# public_ASADASIoTV1.net
KiCad netlist of a schematic drawn in EAGLE
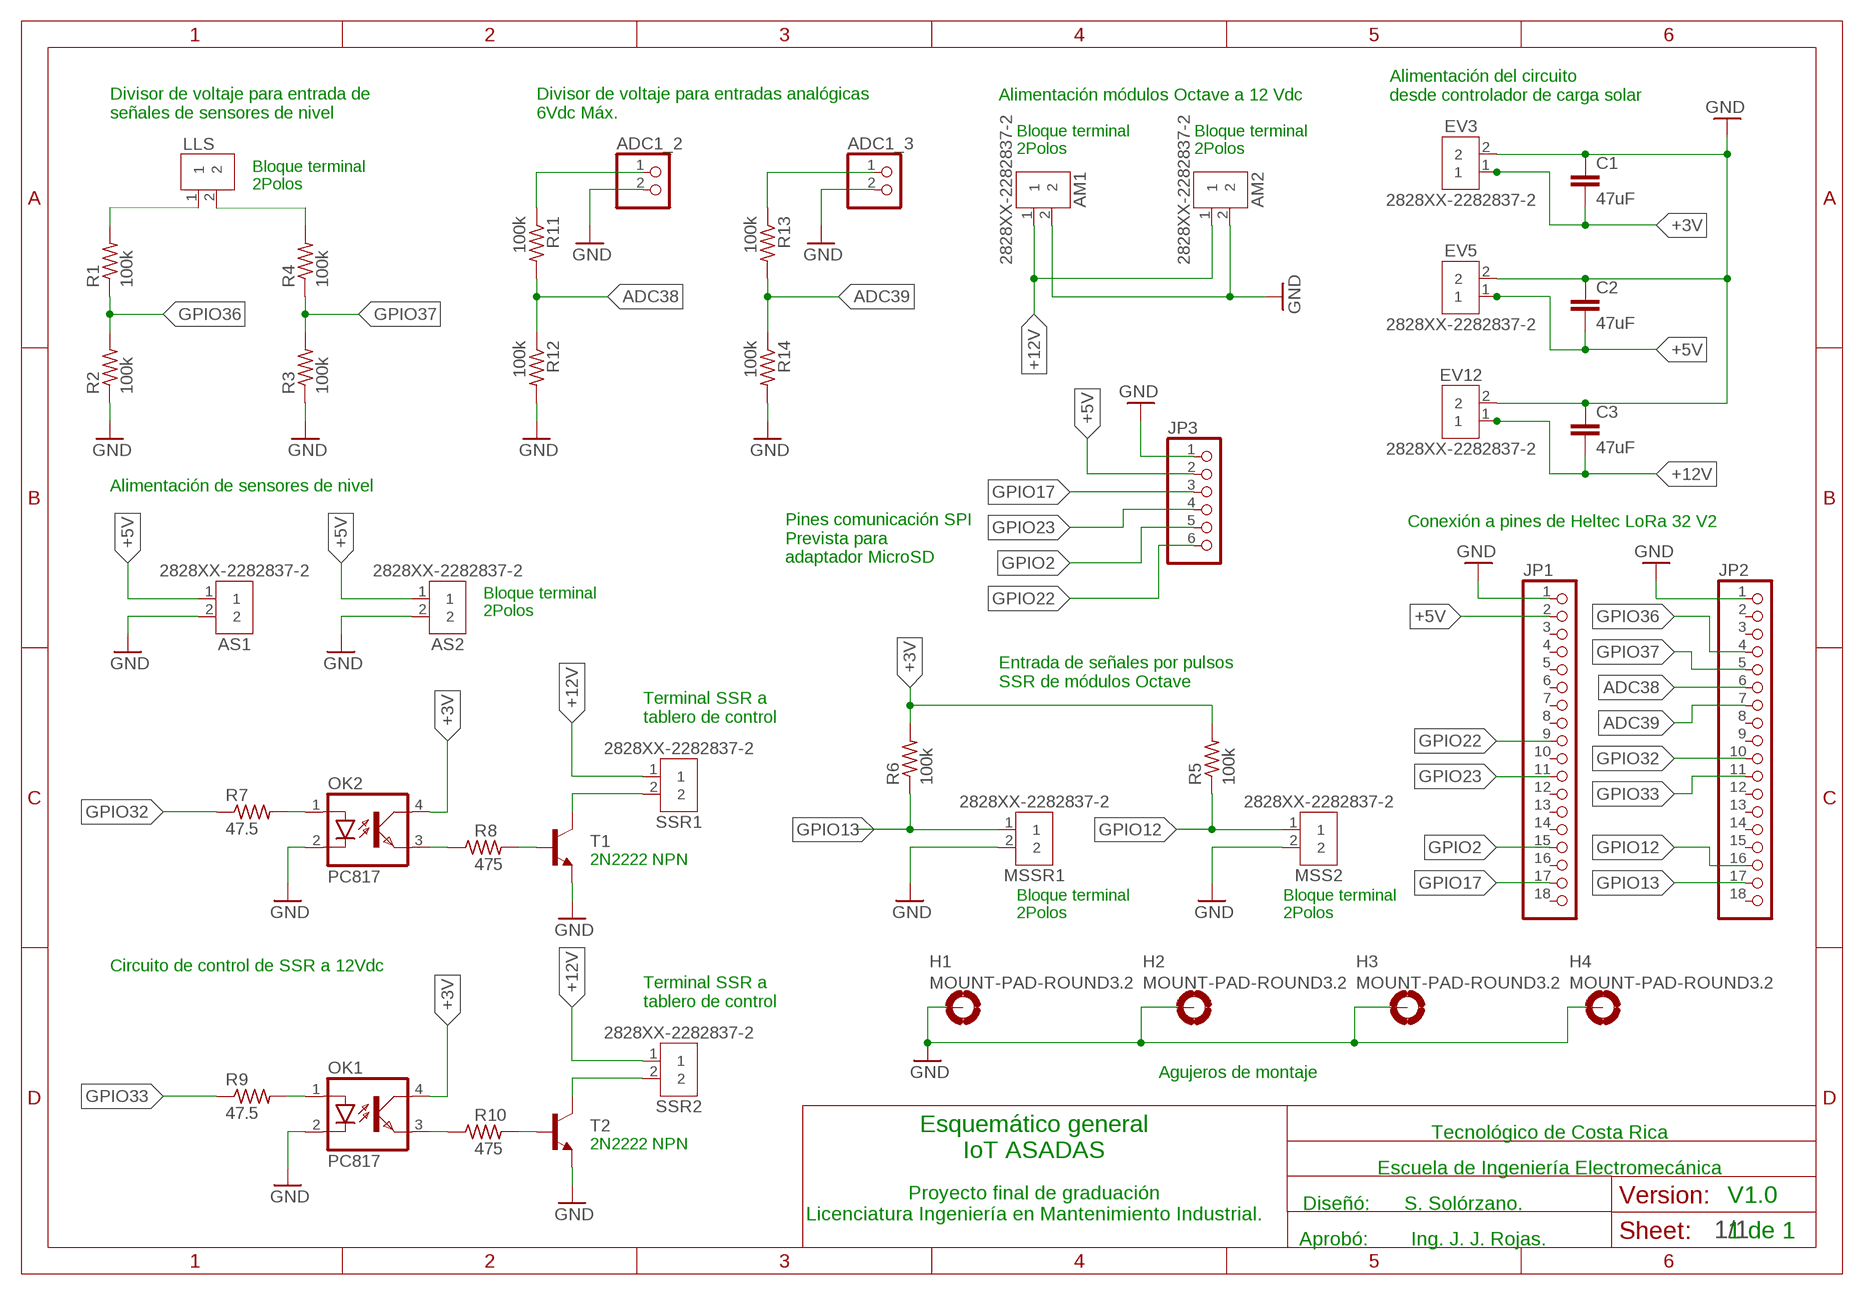
[diagram p0: schematic, sheet 1]

(export (version "E")
  (design (tool "Eeschema 10.0.6"))
  (components
    (comp (ref "ADC1_2")
      (value "PINHD-1X2")
      (footprint "eagle-import:1X02")
      (libsource (lib "eagle-import") (part "PINHD-1X2"))
    )
    (comp (ref "ADC1_3")
      (value "PINHD-1X2")
      (footprint "eagle-import:1X02")
      (libsource (lib "eagle-import") (part "PINHD-1X2"))
    )
    (comp (ref "AM1")
      (value "2828XX-2282837-2")
      (footprint "eagle-import:TERMBLK_508-2N")
      (fields (field (name "MANUFACTURER") "TE Connectivity") (field (name "MPN") "282837-2"))
      (libsource (lib "eagle-import") (part "2828XX-2282837-2"))
    )
    (comp (ref "AM2")
      (value "2828XX-2282837-2")
      (footprint "eagle-import:TERMBLK_508-2N")
      (fields (field (name "MANUFACTURER") "TE Connectivity") (field (name "MPN") "282837-2"))
      (libsource (lib "eagle-import") (part "2828XX-2282837-2"))
    )
    (comp (ref "AS1")
      (value "2828XX-2282837-2")
      (footprint "eagle-import:TERMBLK_508-2N")
      (fields (field (name "MANUFACTURER") "TE Connectivity") (field (name "MPN") "282837-2"))
      (libsource (lib "eagle-import") (part "2828XX-2282837-2"))
    )
    (comp (ref "AS2")
      (value "2828XX-2282837-2")
      (footprint "eagle-import:TERMBLK_508-2N")
      (fields (field (name "MANUFACTURER") "TE Connectivity") (field (name "MPN") "282837-2"))
      (libsource (lib "eagle-import") (part "2828XX-2282837-2"))
    )
    (comp (ref "C1")
      (value "47uF")
      (footprint "eagle-import:C2.5-5")
      (libsource (lib "eagle-import") (part "C2.5/5"))
    )
    (comp (ref "C2")
      (value "47uF")
      (footprint "eagle-import:C2.5-5")
      (libsource (lib "eagle-import") (part "C2.5/5"))
    )
    (comp (ref "C3")
      (value "47uF")
      (footprint "eagle-import:C2.5-5")
      (libsource (lib "eagle-import") (part "C2.5/5"))
    )
    (comp (ref "EV3")
      (value "2828XX-2282837-2")
      (footprint "eagle-import:TERMBLK_508-2N")
      (fields (field (name "MANUFACTURER") "TE Connectivity") (field (name "MPN") "282837-2"))
      (libsource (lib "eagle-import") (part "2828XX-2282837-2"))
    )
    (comp (ref "EV5")
      (value "2828XX-2282837-2")
      (footprint "eagle-import:TERMBLK_508-2N")
      (fields (field (name "MANUFACTURER") "TE Connectivity") (field (name "MPN") "282837-2"))
      (libsource (lib "eagle-import") (part "2828XX-2282837-2"))
    )
    (comp (ref "EV12")
      (value "2828XX-2282837-2")
      (footprint "eagle-import:TERMBLK_508-2N")
      (fields (field (name "MANUFACTURER") "TE Connectivity") (field (name "MPN") "282837-2"))
      (libsource (lib "eagle-import") (part "2828XX-2282837-2"))
    )
    (comp (ref "H1")
      (value "MOUNT-PAD-ROUND3.2")
      (footprint "eagle-import:3,2-PAD")
      (libsource (lib "eagle-import") (part "MOUNT-PAD-ROUND3.2"))
    )
    (comp (ref "H2")
      (value "MOUNT-PAD-ROUND3.2")
      (footprint "eagle-import:3,2-PAD")
      (libsource (lib "eagle-import") (part "MOUNT-PAD-ROUND3.2"))
    )
    (comp (ref "H3")
      (value "MOUNT-PAD-ROUND3.2")
      (footprint "eagle-import:3,2-PAD")
      (libsource (lib "eagle-import") (part "MOUNT-PAD-ROUND3.2"))
    )
    (comp (ref "H4")
      (value "MOUNT-PAD-ROUND3.2")
      (footprint "eagle-import:3,2-PAD")
      (libsource (lib "eagle-import") (part "MOUNT-PAD-ROUND3.2"))
    )
    (comp (ref "JP1")
      (value "PINHD-1X18")
      (footprint "eagle-import:1X18")
      (libsource (lib "eagle-import") (part "PINHD-1X18"))
    )
    (comp (ref "JP2")
      (value "PINHD-1X18")
      (footprint "eagle-import:1X18")
      (libsource (lib "eagle-import") (part "PINHD-1X18"))
    )
    (comp (ref "JP3")
      (value "PINHD-1X6")
      (footprint "eagle-import:1X06")
      (libsource (lib "eagle-import") (part "PINHD-1X6"))
    )
    (comp (ref "LLS")
      (value "2828XX-2282837-2")
      (footprint "eagle-import:TERMBLK_508-2N")
      (fields (field (name "MANUFACTURER") "TE Connectivity") (field (name "MPN") "282837-2"))
      (libsource (lib "eagle-import") (part "2828XX-2282837-2"))
    )
    (comp (ref "MSS2")
      (value "2828XX-2282837-2")
      (footprint "eagle-import:TERMBLK_508-2N")
      (fields (field (name "MANUFACTURER") "TE Connectivity") (field (name "MPN") "282837-2"))
      (libsource (lib "eagle-import") (part "2828XX-2282837-2"))
    )
    (comp (ref "MSSR1")
      (value "2828XX-2282837-2")
      (footprint "eagle-import:TERMBLK_508-2N")
      (fields (field (name "MANUFACTURER") "TE Connectivity") (field (name "MPN") "282837-2"))
      (libsource (lib "eagle-import") (part "2828XX-2282837-2"))
    )
    (comp (ref "OK1")
      (value "PC817")
      (footprint "eagle-import:DIL04")
      (fields (field (name "MPN") "PC817X4J000F"))
      (libsource (lib "eagle-import") (part "PC817"))
    )
    (comp (ref "OK2")
      (value "PC817")
      (footprint "eagle-import:DIL04")
      (fields (field (name "MPN") "PC817X4J000F"))
      (libsource (lib "eagle-import") (part "PC817"))
    )
    (comp (ref "R1")
      (value "100k")
      (footprint "eagle-import:R0805")
      (libsource (lib "eagle-import") (part "R-US_R0805"))
    )
    (comp (ref "R2")
      (value "100k")
      (footprint "eagle-import:R0805")
      (libsource (lib "eagle-import") (part "R-US_R0805"))
    )
    (comp (ref "R3")
      (value "100k")
      (footprint "eagle-import:R0805")
      (libsource (lib "eagle-import") (part "R-US_R0805"))
    )
    (comp (ref "R4")
      (value "100k")
      (footprint "eagle-import:R0805")
      (libsource (lib "eagle-import") (part "R-US_R0805"))
    )
    (comp (ref "R5")
      (value "100k")
      (footprint "eagle-import:R0805")
      (libsource (lib "eagle-import") (part "R-US_R0805"))
    )
    (comp (ref "R6")
      (value "100k")
      (footprint "eagle-import:R0805")
      (libsource (lib "eagle-import") (part "R-US_R0805"))
    )
    (comp (ref "R7")
      (value "47.5")
      (footprint "eagle-import:R0805")
      (libsource (lib "eagle-import") (part "R-US_R0805"))
    )
    (comp (ref "R8")
      (value "475")
      (footprint "eagle-import:R0805")
      (libsource (lib "eagle-import") (part "R-US_R0805"))
    )
    (comp (ref "R9")
      (value "47.5")
      (footprint "eagle-import:R0805")
      (libsource (lib "eagle-import") (part "R-US_R0805"))
    )
    (comp (ref "R10")
      (value "475")
      (footprint "eagle-import:R0805")
      (libsource (lib "eagle-import") (part "R-US_R0805"))
    )
    (comp (ref "R11")
      (value "100k")
      (footprint "eagle-import:R0805")
      (libsource (lib "eagle-import") (part "R-US_R0805"))
    )
    (comp (ref "R12")
      (value "100k")
      (footprint "eagle-import:R0805")
      (libsource (lib "eagle-import") (part "R-US_R0805"))
    )
    (comp (ref "R13")
      (value "100k")
      (footprint "eagle-import:R0805")
      (libsource (lib "eagle-import") (part "R-US_R0805"))
    )
    (comp (ref "R14")
      (value "100k")
      (footprint "eagle-import:R0805")
      (libsource (lib "eagle-import") (part "R-US_R0805"))
    )
    (comp (ref "SSR1")
      (value "2828XX-2282837-2")
      (footprint "eagle-import:TERMBLK_508-2N")
      (fields (field (name "MANUFACTURER") "TE Connectivity") (field (name "MPN") "282837-2"))
      (libsource (lib "eagle-import") (part "2828XX-2282837-2"))
    )
    (comp (ref "SSR2")
      (value "2828XX-2282837-2")
      (footprint "eagle-import:TERMBLK_508-2N")
      (fields (field (name "MANUFACTURER") "TE Connectivity") (field (name "MPN") "282837-2"))
      (libsource (lib "eagle-import") (part "2828XX-2282837-2"))
    )
    (comp (ref "T1")
      (value "2N3904")
      (footprint "eagle-import:TO92")
      (libsource (lib "eagle-import") (part "2N3904"))
    )
    (comp (ref "T2")
      (value "2N3904")
      (footprint "eagle-import:TO92")
      (libsource (lib "eagle-import") (part "2N3904"))
    )
  )
  (nets
    (net (code "1") (name "+3V") (class "Default")
      (node (ref "C1") (pin "2") (pinfunction "2_2") (pintype "passive"))
      (node (ref "EV3") (pin "1") (pinfunction "1_1") (pintype "bidirectional"))
      (node (ref "OK1") (pin "4") (pinfunction "COL_4") (pintype "passive"))
      (node (ref "OK2") (pin "4") (pinfunction "COL_4") (pintype "passive"))
      (node (ref "R5") (pin "2") (pinfunction "2_2") (pintype "passive"))
      (node (ref "R6") (pin "2") (pinfunction "2_2") (pintype "passive"))
    )
    (net (code "2") (name "+5V") (class "Default")
      (node (ref "AS1") (pin "1") (pinfunction "1_1") (pintype "bidirectional"))
      (node (ref "AS2") (pin "1") (pinfunction "1_1") (pintype "bidirectional"))
      (node (ref "C2") (pin "2") (pinfunction "2_2") (pintype "passive"))
      (node (ref "EV5") (pin "1") (pinfunction "1_1") (pintype "bidirectional"))
      (node (ref "JP1") (pin "2") (pinfunction "2_2") (pintype "passive"))
      (node (ref "JP3") (pin "2") (pinfunction "2_2") (pintype "passive"))
    )
    (net (code "3") (name "+12V") (class "Default")
      (node (ref "AM1") (pin "1") (pinfunction "1_1") (pintype "bidirectional"))
      (node (ref "AM2") (pin "1") (pinfunction "1_1") (pintype "bidirectional"))
      (node (ref "C3") (pin "2") (pinfunction "2_2") (pintype "passive"))
      (node (ref "EV12") (pin "1") (pinfunction "1_1") (pintype "bidirectional"))
      (node (ref "SSR1") (pin "1") (pinfunction "1_1") (pintype "bidirectional"))
      (node (ref "SSR2") (pin "1") (pinfunction "1_1") (pintype "bidirectional"))
    )
    (net (code "4") (name "ADC38") (class "Default")
      (node (ref "JP2") (pin "6") (pinfunction "6_6") (pintype "passive"))
      (node (ref "R11") (pin "2") (pinfunction "2_2") (pintype "passive"))
      (node (ref "R12") (pin "1") (pinfunction "1_1") (pintype "passive"))
    )
    (net (code "5") (name "ADC39") (class "Default")
      (node (ref "JP2") (pin "7") (pinfunction "7_7") (pintype "passive"))
      (node (ref "R13") (pin "2") (pinfunction "2_2") (pintype "passive"))
      (node (ref "R14") (pin "1") (pinfunction "1_1") (pintype "passive"))
    )
    (net (code "6") (name "GND") (class "Default")
      (node (ref "ADC1_2") (pin "2") (pinfunction "2_2") (pintype "passive"))
      (node (ref "ADC1_3") (pin "2") (pinfunction "2_2") (pintype "passive"))
      (node (ref "AM1") (pin "2") (pinfunction "2_2") (pintype "bidirectional"))
      (node (ref "AM2") (pin "2") (pinfunction "2_2") (pintype "bidirectional"))
      (node (ref "AS1") (pin "2") (pinfunction "2_2") (pintype "bidirectional"))
      (node (ref "AS2") (pin "2") (pinfunction "2_2") (pintype "bidirectional"))
      (node (ref "C1") (pin "1") (pinfunction "1_1") (pintype "passive"))
      (node (ref "C2") (pin "1") (pinfunction "1_1") (pintype "passive"))
      (node (ref "C3") (pin "1") (pinfunction "1_1") (pintype "passive"))
      (node (ref "EV12") (pin "2") (pinfunction "2_2") (pintype "bidirectional"))
      (node (ref "EV3") (pin "2") (pinfunction "2_2") (pintype "bidirectional"))
      (node (ref "EV5") (pin "2") (pinfunction "2_2") (pintype "bidirectional"))
      (node (ref "H1") (pin "B3,2") (pinfunction "MOUNT_B3,2") (pintype "passive"))
      (node (ref "H2") (pin "B3,2") (pinfunction "MOUNT_B3,2") (pintype "passive"))
      (node (ref "H3") (pin "B3,2") (pinfunction "MOUNT_B3,2") (pintype "passive"))
      (node (ref "H4") (pin "B3,2") (pinfunction "MOUNT_B3,2") (pintype "passive"))
      (node (ref "JP1") (pin "1") (pinfunction "1_1") (pintype "passive"))
      (node (ref "JP2") (pin "1") (pinfunction "1_1") (pintype "passive"))
      (node (ref "JP3") (pin "1") (pinfunction "1_1") (pintype "passive"))
      (node (ref "MSS2") (pin "2") (pinfunction "2_2") (pintype "bidirectional"))
      (node (ref "MSSR1") (pin "2") (pinfunction "2_2") (pintype "bidirectional"))
      (node (ref "OK1") (pin "2") (pinfunction "C_2") (pintype "passive"))
      (node (ref "OK2") (pin "2") (pinfunction "C_2") (pintype "passive"))
      (node (ref "R12") (pin "2") (pinfunction "2_2") (pintype "passive"))
      (node (ref "R14") (pin "2") (pinfunction "2_2") (pintype "passive"))
      (node (ref "R2") (pin "1") (pinfunction "1_1") (pintype "passive"))
      (node (ref "R3") (pin "1") (pinfunction "1_1") (pintype "passive"))
      (node (ref "T1") (pin "3") (pinfunction "E_3") (pintype "passive"))
      (node (ref "T2") (pin "3") (pinfunction "E_3") (pintype "passive"))
    )
    (net (code "7") (name "GPIO2") (class "Default")
      (node (ref "JP1") (pin "15") (pinfunction "15_15") (pintype "passive"))
      (node (ref "JP3") (pin "5") (pinfunction "5_5") (pintype "passive"))
    )
    (net (code "8") (name "GPIO12") (class "Default")
      (node (ref "JP2") (pin "16") (pinfunction "16_16") (pintype "passive"))
      (node (ref "MSS2") (pin "1") (pinfunction "1_1") (pintype "bidirectional"))
      (node (ref "R5") (pin "1") (pinfunction "1_1") (pintype "passive"))
    )
    (net (code "9") (name "GPIO13") (class "Default")
      (node (ref "JP2") (pin "17") (pinfunction "17_17") (pintype "passive"))
      (node (ref "MSSR1") (pin "1") (pinfunction "1_1") (pintype "bidirectional"))
      (node (ref "R6") (pin "1") (pinfunction "1_1") (pintype "passive"))
    )
    (net (code "10") (name "GPIO17") (class "Default")
      (node (ref "JP1") (pin "17") (pinfunction "17_17") (pintype "passive"))
      (node (ref "JP3") (pin "3") (pinfunction "3_3") (pintype "passive"))
    )
    (net (code "11") (name "GPIO22") (class "Default")
      (node (ref "JP1") (pin "9") (pinfunction "9_9") (pintype "passive"))
      (node (ref "JP3") (pin "6") (pinfunction "6_6") (pintype "passive"))
    )
    (net (code "12") (name "GPIO23") (class "Default")
      (node (ref "JP1") (pin "11") (pinfunction "11_11") (pintype "passive"))
      (node (ref "JP3") (pin "4") (pinfunction "4_4") (pintype "passive"))
    )
    (net (code "13") (name "GPIO32") (class "Default")
      (node (ref "JP2") (pin "10") (pinfunction "10_10") (pintype "passive"))
      (node (ref "R7") (pin "1") (pinfunction "1_1") (pintype "passive"))
    )
    (net (code "14") (name "GPIO33") (class "Default")
      (node (ref "JP2") (pin "11") (pinfunction "11_11") (pintype "passive"))
      (node (ref "R9") (pin "1") (pinfunction "1_1") (pintype "passive"))
    )
    (net (code "15") (name "GPIO36") (class "Default")
      (node (ref "JP2") (pin "4") (pinfunction "4_4") (pintype "passive"))
      (node (ref "R1") (pin "1") (pinfunction "1_1") (pintype "passive"))
      (node (ref "R2") (pin "2") (pinfunction "2_2") (pintype "passive"))
    )
    (net (code "16") (name "GPIO37") (class "Default")
      (node (ref "JP2") (pin "5") (pinfunction "5_5") (pintype "passive"))
      (node (ref "R3") (pin "2") (pinfunction "2_2") (pintype "passive"))
      (node (ref "R4") (pin "1") (pinfunction "1_1") (pintype "passive"))
    )
    (net (code "17") (name "Net-(ADC1_2-Pad1)") (class "Default")
      (node (ref "ADC1_2") (pin "1") (pinfunction "1_1") (pintype "passive"))
      (node (ref "R11") (pin "1") (pinfunction "1_1") (pintype "passive"))
    )
    (net (code "18") (name "Net-(ADC1_3-Pad1)") (class "Default")
      (node (ref "ADC1_3") (pin "1") (pinfunction "1_1") (pintype "passive"))
      (node (ref "R13") (pin "1") (pinfunction "1_1") (pintype "passive"))
    )
    (net (code "19") (name "Net-(LLS-Pad1)") (class "Default")
      (node (ref "LLS") (pin "1") (pinfunction "1_1") (pintype "bidirectional"))
      (node (ref "R1") (pin "2") (pinfunction "2_2") (pintype "passive"))
    )
    (net (code "20") (name "Net-(LLS-Pad2)") (class "Default")
      (node (ref "LLS") (pin "2") (pinfunction "2_2") (pintype "bidirectional"))
      (node (ref "R4") (pin "2") (pinfunction "2_2") (pintype "passive"))
    )
    (net (code "21") (name "Net-(OK1-A)") (class "Default")
      (node (ref "OK1") (pin "1") (pinfunction "A_1") (pintype "passive"))
      (node (ref "R9") (pin "2") (pinfunction "2_2") (pintype "passive"))
    )
    (net (code "22") (name "Net-(OK1-EMIT)") (class "Default")
      (node (ref "OK1") (pin "3") (pinfunction "EMIT_3") (pintype "passive"))
      (node (ref "R10") (pin "1") (pinfunction "1_1") (pintype "passive"))
    )
    (net (code "23") (name "Net-(OK2-A)") (class "Default")
      (node (ref "OK2") (pin "1") (pinfunction "A_1") (pintype "passive"))
      (node (ref "R7") (pin "2") (pinfunction "2_2") (pintype "passive"))
    )
    (net (code "24") (name "Net-(OK2-EMIT)") (class "Default")
      (node (ref "OK2") (pin "3") (pinfunction "EMIT_3") (pintype "passive"))
      (node (ref "R8") (pin "1") (pinfunction "1_1") (pintype "passive"))
    )
    (net (code "25") (name "Net-(T1-B)") (class "Default")
      (node (ref "R8") (pin "2") (pinfunction "2_2") (pintype "passive"))
      (node (ref "T1") (pin "2") (pinfunction "B_2") (pintype "passive"))
    )
    (net (code "26") (name "Net-(T1-C)") (class "Default")
      (node (ref "SSR1") (pin "2") (pinfunction "2_2") (pintype "bidirectional"))
      (node (ref "T1") (pin "1") (pinfunction "C_1") (pintype "passive"))
    )
    (net (code "27") (name "Net-(T2-B)") (class "Default")
      (node (ref "R10") (pin "2") (pinfunction "2_2") (pintype "passive"))
      (node (ref "T2") (pin "2") (pinfunction "B_2") (pintype "passive"))
    )
    (net (code "28") (name "Net-(T2-C)") (class "Default")
      (node (ref "SSR2") (pin "2") (pinfunction "2_2") (pintype "bidirectional"))
      (node (ref "T2") (pin "1") (pinfunction "C_1") (pintype "passive"))
    )
    (net (code "29") (name "unconnected-(JP1-Pad3)") (class "Default")
      (node (ref "JP1") (pin "3") (pinfunction "3_3") (pintype "passive"))
    )
    (net (code "30") (name "unconnected-(JP1-Pad4)") (class "Default")
      (node (ref "JP1") (pin "4") (pinfunction "4_4") (pintype "passive"))
    )
    (net (code "31") (name "unconnected-(JP1-Pad5)") (class "Default")
      (node (ref "JP1") (pin "5") (pinfunction "5_5") (pintype "passive"))
    )
    (net (code "32") (name "unconnected-(JP1-Pad6)") (class "Default")
      (node (ref "JP1") (pin "6") (pinfunction "6_6") (pintype "passive"))
    )
    (net (code "33") (name "unconnected-(JP1-Pad7)") (class "Default")
      (node (ref "JP1") (pin "7") (pinfunction "7_7") (pintype "passive"))
    )
    (net (code "34") (name "unconnected-(JP1-Pad8)") (class "Default")
      (node (ref "JP1") (pin "8") (pinfunction "8_8") (pintype "passive"))
    )
    (net (code "35") (name "unconnected-(JP1-Pad10)") (class "Default")
      (node (ref "JP1") (pin "10") (pinfunction "10_10") (pintype "passive"))
    )
    (net (code "36") (name "unconnected-(JP1-Pad12)") (class "Default")
      (node (ref "JP1") (pin "12") (pinfunction "12_12") (pintype "passive"))
    )
    (net (code "37") (name "unconnected-(JP1-Pad13)") (class "Default")
      (node (ref "JP1") (pin "13") (pinfunction "13_13") (pintype "passive"))
    )
    (net (code "38") (name "unconnected-(JP1-Pad14)") (class "Default")
      (node (ref "JP1") (pin "14") (pinfunction "14_14") (pintype "passive"))
    )
    (net (code "39") (name "unconnected-(JP1-Pad16)") (class "Default")
      (node (ref "JP1") (pin "16") (pinfunction "16_16") (pintype "passive"))
    )
    (net (code "40") (name "unconnected-(JP1-Pad18)") (class "Default")
      (node (ref "JP1") (pin "18") (pinfunction "18_18") (pintype "passive"))
    )
    (net (code "41") (name "unconnected-(JP2-Pad2)") (class "Default")
      (node (ref "JP2") (pin "2") (pinfunction "2_2") (pintype "passive"))
    )
    (net (code "42") (name "unconnected-(JP2-Pad3)") (class "Default")
      (node (ref "JP2") (pin "3") (pinfunction "3_3") (pintype "passive"))
    )
    (net (code "43") (name "unconnected-(JP2-Pad8)") (class "Default")
      (node (ref "JP2") (pin "8") (pinfunction "8_8") (pintype "passive"))
    )
    (net (code "44") (name "unconnected-(JP2-Pad9)") (class "Default")
      (node (ref "JP2") (pin "9") (pinfunction "9_9") (pintype "passive"))
    )
    (net (code "45") (name "unconnected-(JP2-Pad12)") (class "Default")
      (node (ref "JP2") (pin "12") (pinfunction "12_12") (pintype "passive"))
    )
    (net (code "46") (name "unconnected-(JP2-Pad13)") (class "Default")
      (node (ref "JP2") (pin "13") (pinfunction "13_13") (pintype "passive"))
    )
    (net (code "47") (name "unconnected-(JP2-Pad14)") (class "Default")
      (node (ref "JP2") (pin "14") (pinfunction "14_14") (pintype "passive"))
    )
    (net (code "48") (name "unconnected-(JP2-Pad15)") (class "Default")
      (node (ref "JP2") (pin "15") (pinfunction "15_15") (pintype "passive"))
    )
    (net (code "49") (name "unconnected-(JP2-Pad18)") (class "Default")
      (node (ref "JP2") (pin "18") (pinfunction "18_18") (pintype "passive"))
    )
  )
)
